# 8_bit.net
KiCad netlist of a schematic drawn in EAGLE
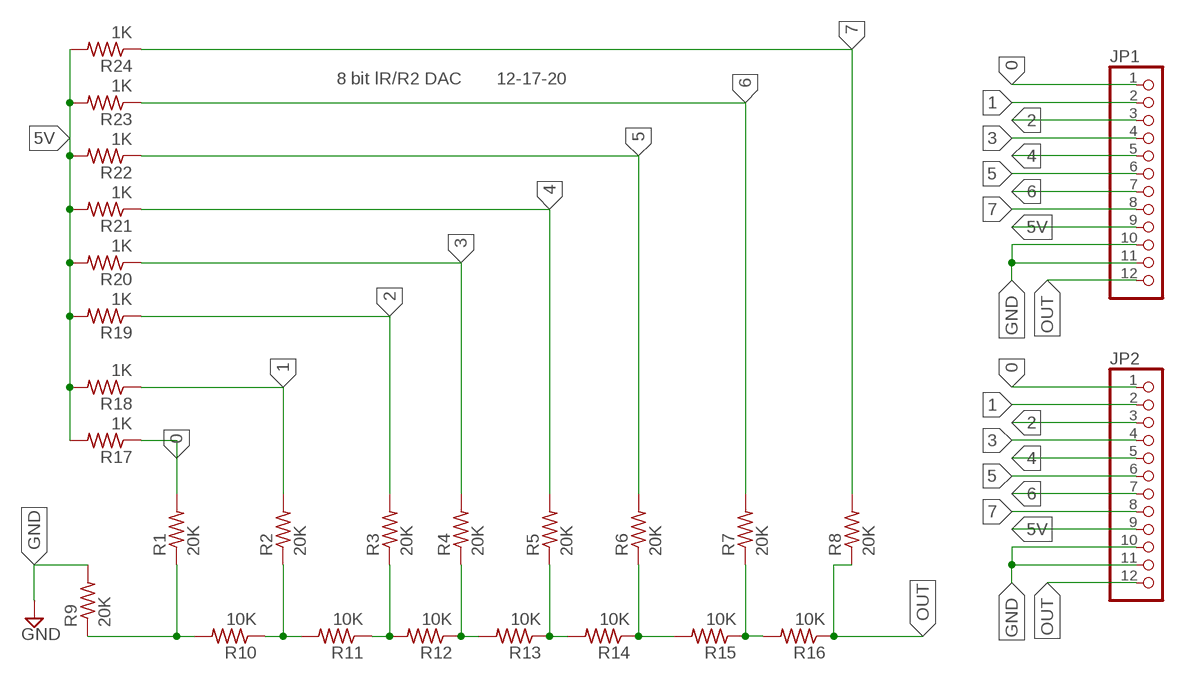
[diagram p0: schematic, sheet 1]

(export (version "E")
  (design (tool "Eeschema 10.0.6"))
  (components
    (comp (ref "JP1")
      (value "PINHD-1X12")
      (footprint "eagle-import:1X12")
      (libsource (lib "eagle-import") (part "PINHD-1X12"))
    )
    (comp (ref "JP2")
      (value "PINHD-1X12")
      (footprint "eagle-import:1X12")
      (libsource (lib "eagle-import") (part "PINHD-1X12"))
    )
    (comp (ref "R1")
      (value "20K")
      (footprint "eagle-import:0204_7")
      (libsource (lib "eagle-import") (part "R-US_0204/7"))
    )
    (comp (ref "R2")
      (value "20K")
      (footprint "eagle-import:0204_7")
      (libsource (lib "eagle-import") (part "R-US_0204/7"))
    )
    (comp (ref "R3")
      (value "20K")
      (footprint "eagle-import:0204_7")
      (libsource (lib "eagle-import") (part "R-US_0204/7"))
    )
    (comp (ref "R4")
      (value "20K")
      (footprint "eagle-import:0204_7")
      (libsource (lib "eagle-import") (part "R-US_0204/7"))
    )
    (comp (ref "R5")
      (value "20K")
      (footprint "eagle-import:0204_7")
      (libsource (lib "eagle-import") (part "R-US_0204/7"))
    )
    (comp (ref "R6")
      (value "20K")
      (footprint "eagle-import:0204_7")
      (libsource (lib "eagle-import") (part "R-US_0204/7"))
    )
    (comp (ref "R7")
      (value "20K")
      (footprint "eagle-import:0204_7")
      (libsource (lib "eagle-import") (part "R-US_0204/7"))
    )
    (comp (ref "R8")
      (value "20K")
      (footprint "eagle-import:0204_7")
      (libsource (lib "eagle-import") (part "R-US_0204/7"))
    )
    (comp (ref "R9")
      (value "20K")
      (footprint "eagle-import:0204_7")
      (libsource (lib "eagle-import") (part "R-US_0204/7"))
    )
    (comp (ref "R10")
      (value "10K")
      (footprint "eagle-import:0204_7")
      (libsource (lib "eagle-import") (part "R-US_0204/7"))
    )
    (comp (ref "R11")
      (value "10K")
      (footprint "eagle-import:0204_7")
      (libsource (lib "eagle-import") (part "R-US_0204/7"))
    )
    (comp (ref "R12")
      (value "10K")
      (footprint "eagle-import:0204_7")
      (libsource (lib "eagle-import") (part "R-US_0204/7"))
    )
    (comp (ref "R13")
      (value "10K")
      (footprint "eagle-import:0204_7")
      (libsource (lib "eagle-import") (part "R-US_0204/7"))
    )
    (comp (ref "R14")
      (value "10K")
      (footprint "eagle-import:0204_7")
      (libsource (lib "eagle-import") (part "R-US_0204/7"))
    )
    (comp (ref "R15")
      (value "10K")
      (footprint "eagle-import:0204_7")
      (libsource (lib "eagle-import") (part "R-US_0204/7"))
    )
    (comp (ref "R16")
      (value "10K")
      (footprint "eagle-import:0204_7")
      (libsource (lib "eagle-import") (part "R-US_0204/7"))
    )
    (comp (ref "R17")
      (value "1K")
      (footprint "eagle-import:0204_7")
      (libsource (lib "eagle-import") (part "R-US_0204/7"))
    )
    (comp (ref "R18")
      (value "1K")
      (footprint "eagle-import:0204_7")
      (libsource (lib "eagle-import") (part "R-US_0204/7"))
    )
    (comp (ref "R19")
      (value "1K")
      (footprint "eagle-import:0204_7")
      (libsource (lib "eagle-import") (part "R-US_0204/7"))
    )
    (comp (ref "R20")
      (value "1K")
      (footprint "eagle-import:0204_7")
      (libsource (lib "eagle-import") (part "R-US_0204/7"))
    )
    (comp (ref "R21")
      (value "1K")
      (footprint "eagle-import:0204_7")
      (libsource (lib "eagle-import") (part "R-US_0204/7"))
    )
    (comp (ref "R22")
      (value "1K")
      (footprint "eagle-import:0204_7")
      (libsource (lib "eagle-import") (part "R-US_0204/7"))
    )
    (comp (ref "R23")
      (value "1K")
      (footprint "eagle-import:0204_7")
      (libsource (lib "eagle-import") (part "R-US_0204/7"))
    )
    (comp (ref "R24")
      (value "1K")
      (footprint "eagle-import:0204_7")
      (libsource (lib "eagle-import") (part "R-US_0204/7"))
    )
  )
  (nets
    (net (code "1") (name "0") (class "Default")
      (node (ref "JP1") (pin "1") (pinfunction "1_1") (pintype "passive"))
      (node (ref "JP2") (pin "1") (pinfunction "1_1") (pintype "passive"))
      (node (ref "R1") (pin "2") (pinfunction "2_2") (pintype "passive"))
      (node (ref "R17") (pin "1") (pinfunction "1_1") (pintype "passive"))
    )
    (net (code "2") (name "1") (class "Default")
      (node (ref "JP1") (pin "2") (pinfunction "2_2") (pintype "passive"))
      (node (ref "JP2") (pin "2") (pinfunction "2_2") (pintype "passive"))
      (node (ref "R18") (pin "1") (pinfunction "1_1") (pintype "passive"))
      (node (ref "R2") (pin "2") (pinfunction "2_2") (pintype "passive"))
    )
    (net (code "3") (name "2") (class "Default")
      (node (ref "JP1") (pin "3") (pinfunction "3_3") (pintype "passive"))
      (node (ref "JP2") (pin "3") (pinfunction "3_3") (pintype "passive"))
      (node (ref "R19") (pin "1") (pinfunction "1_1") (pintype "passive"))
      (node (ref "R3") (pin "2") (pinfunction "2_2") (pintype "passive"))
    )
    (net (code "4") (name "3") (class "Default")
      (node (ref "JP1") (pin "4") (pinfunction "4_4") (pintype "passive"))
      (node (ref "JP2") (pin "4") (pinfunction "4_4") (pintype "passive"))
      (node (ref "R20") (pin "1") (pinfunction "1_1") (pintype "passive"))
      (node (ref "R4") (pin "2") (pinfunction "2_2") (pintype "passive"))
    )
    (net (code "5") (name "4") (class "Default")
      (node (ref "JP1") (pin "5") (pinfunction "5_5") (pintype "passive"))
      (node (ref "JP2") (pin "5") (pinfunction "5_5") (pintype "passive"))
      (node (ref "R21") (pin "1") (pinfunction "1_1") (pintype "passive"))
      (node (ref "R5") (pin "2") (pinfunction "2_2") (pintype "passive"))
    )
    (net (code "6") (name "5") (class "Default")
      (node (ref "JP1") (pin "6") (pinfunction "6_6") (pintype "passive"))
      (node (ref "JP2") (pin "6") (pinfunction "6_6") (pintype "passive"))
      (node (ref "R22") (pin "1") (pinfunction "1_1") (pintype "passive"))
      (node (ref "R6") (pin "2") (pinfunction "2_2") (pintype "passive"))
    )
    (net (code "7") (name "5V") (class "Default")
      (node (ref "JP1") (pin "9") (pinfunction "9_9") (pintype "passive"))
      (node (ref "JP2") (pin "9") (pinfunction "9_9") (pintype "passive"))
      (node (ref "R17") (pin "2") (pinfunction "2_2") (pintype "passive"))
      (node (ref "R18") (pin "2") (pinfunction "2_2") (pintype "passive"))
      (node (ref "R19") (pin "2") (pinfunction "2_2") (pintype "passive"))
      (node (ref "R20") (pin "2") (pinfunction "2_2") (pintype "passive"))
      (node (ref "R21") (pin "2") (pinfunction "2_2") (pintype "passive"))
      (node (ref "R22") (pin "2") (pinfunction "2_2") (pintype "passive"))
      (node (ref "R23") (pin "2") (pinfunction "2_2") (pintype "passive"))
      (node (ref "R24") (pin "2") (pinfunction "2_2") (pintype "passive"))
    )
    (net (code "8") (name "6") (class "Default")
      (node (ref "JP1") (pin "7") (pinfunction "7_7") (pintype "passive"))
      (node (ref "JP2") (pin "7") (pinfunction "7_7") (pintype "passive"))
      (node (ref "R23") (pin "1") (pinfunction "1_1") (pintype "passive"))
      (node (ref "R7") (pin "2") (pinfunction "2_2") (pintype "passive"))
    )
    (net (code "9") (name "7") (class "Default")
      (node (ref "JP1") (pin "8") (pinfunction "8_8") (pintype "passive"))
      (node (ref "JP2") (pin "8") (pinfunction "8_8") (pintype "passive"))
      (node (ref "R24") (pin "1") (pinfunction "1_1") (pintype "passive"))
      (node (ref "R8") (pin "2") (pinfunction "2_2") (pintype "passive"))
    )
    (net (code "10") (name "GND") (class "Default")
      (node (ref "JP1") (pin "10") (pinfunction "10_10") (pintype "passive"))
      (node (ref "JP1") (pin "11") (pinfunction "11_11") (pintype "passive"))
      (node (ref "JP2") (pin "10") (pinfunction "10_10") (pintype "passive"))
      (node (ref "JP2") (pin "11") (pinfunction "11_11") (pintype "passive"))
      (node (ref "R9") (pin "2") (pinfunction "2_2") (pintype "passive"))
    )
    (net (code "11") (name "Net-(R1-Pad1)") (class "Default")
      (node (ref "R1") (pin "1") (pinfunction "1_1") (pintype "passive"))
      (node (ref "R10") (pin "2") (pinfunction "2_2") (pintype "passive"))
      (node (ref "R9") (pin "1") (pinfunction "1_1") (pintype "passive"))
    )
    (net (code "12") (name "Net-(R10-Pad1)") (class "Default")
      (node (ref "R10") (pin "1") (pinfunction "1_1") (pintype "passive"))
      (node (ref "R11") (pin "2") (pinfunction "2_2") (pintype "passive"))
      (node (ref "R2") (pin "1") (pinfunction "1_1") (pintype "passive"))
    )
    (net (code "13") (name "Net-(R11-Pad1)") (class "Default")
      (node (ref "R11") (pin "1") (pinfunction "1_1") (pintype "passive"))
      (node (ref "R12") (pin "2") (pinfunction "2_2") (pintype "passive"))
      (node (ref "R3") (pin "1") (pinfunction "1_1") (pintype "passive"))
    )
    (net (code "14") (name "Net-(R12-Pad1)") (class "Default")
      (node (ref "R12") (pin "1") (pinfunction "1_1") (pintype "passive"))
      (node (ref "R13") (pin "2") (pinfunction "2_2") (pintype "passive"))
      (node (ref "R4") (pin "1") (pinfunction "1_1") (pintype "passive"))
    )
    (net (code "15") (name "Net-(R13-Pad1)") (class "Default")
      (node (ref "R13") (pin "1") (pinfunction "1_1") (pintype "passive"))
      (node (ref "R14") (pin "2") (pinfunction "2_2") (pintype "passive"))
      (node (ref "R5") (pin "1") (pinfunction "1_1") (pintype "passive"))
    )
    (net (code "16") (name "Net-(R14-Pad1)") (class "Default")
      (node (ref "R14") (pin "1") (pinfunction "1_1") (pintype "passive"))
      (node (ref "R15") (pin "2") (pinfunction "2_2") (pintype "passive"))
      (node (ref "R6") (pin "1") (pinfunction "1_1") (pintype "passive"))
    )
    (net (code "17") (name "Net-(R15-Pad1)") (class "Default")
      (node (ref "R15") (pin "1") (pinfunction "1_1") (pintype "passive"))
      (node (ref "R16") (pin "2") (pinfunction "2_2") (pintype "passive"))
      (node (ref "R7") (pin "1") (pinfunction "1_1") (pintype "passive"))
    )
    (net (code "18") (name "OUT") (class "Default")
      (node (ref "JP1") (pin "12") (pinfunction "12_12") (pintype "passive"))
      (node (ref "JP2") (pin "12") (pinfunction "12_12") (pintype "passive"))
      (node (ref "R16") (pin "1") (pinfunction "1_1") (pintype "passive"))
      (node (ref "R8") (pin "1") (pinfunction "1_1") (pintype "passive"))
    )
  )
)
